# bicyclelab-manager-v4_0.net
KiCad netlist of a schematic drawn in EAGLE
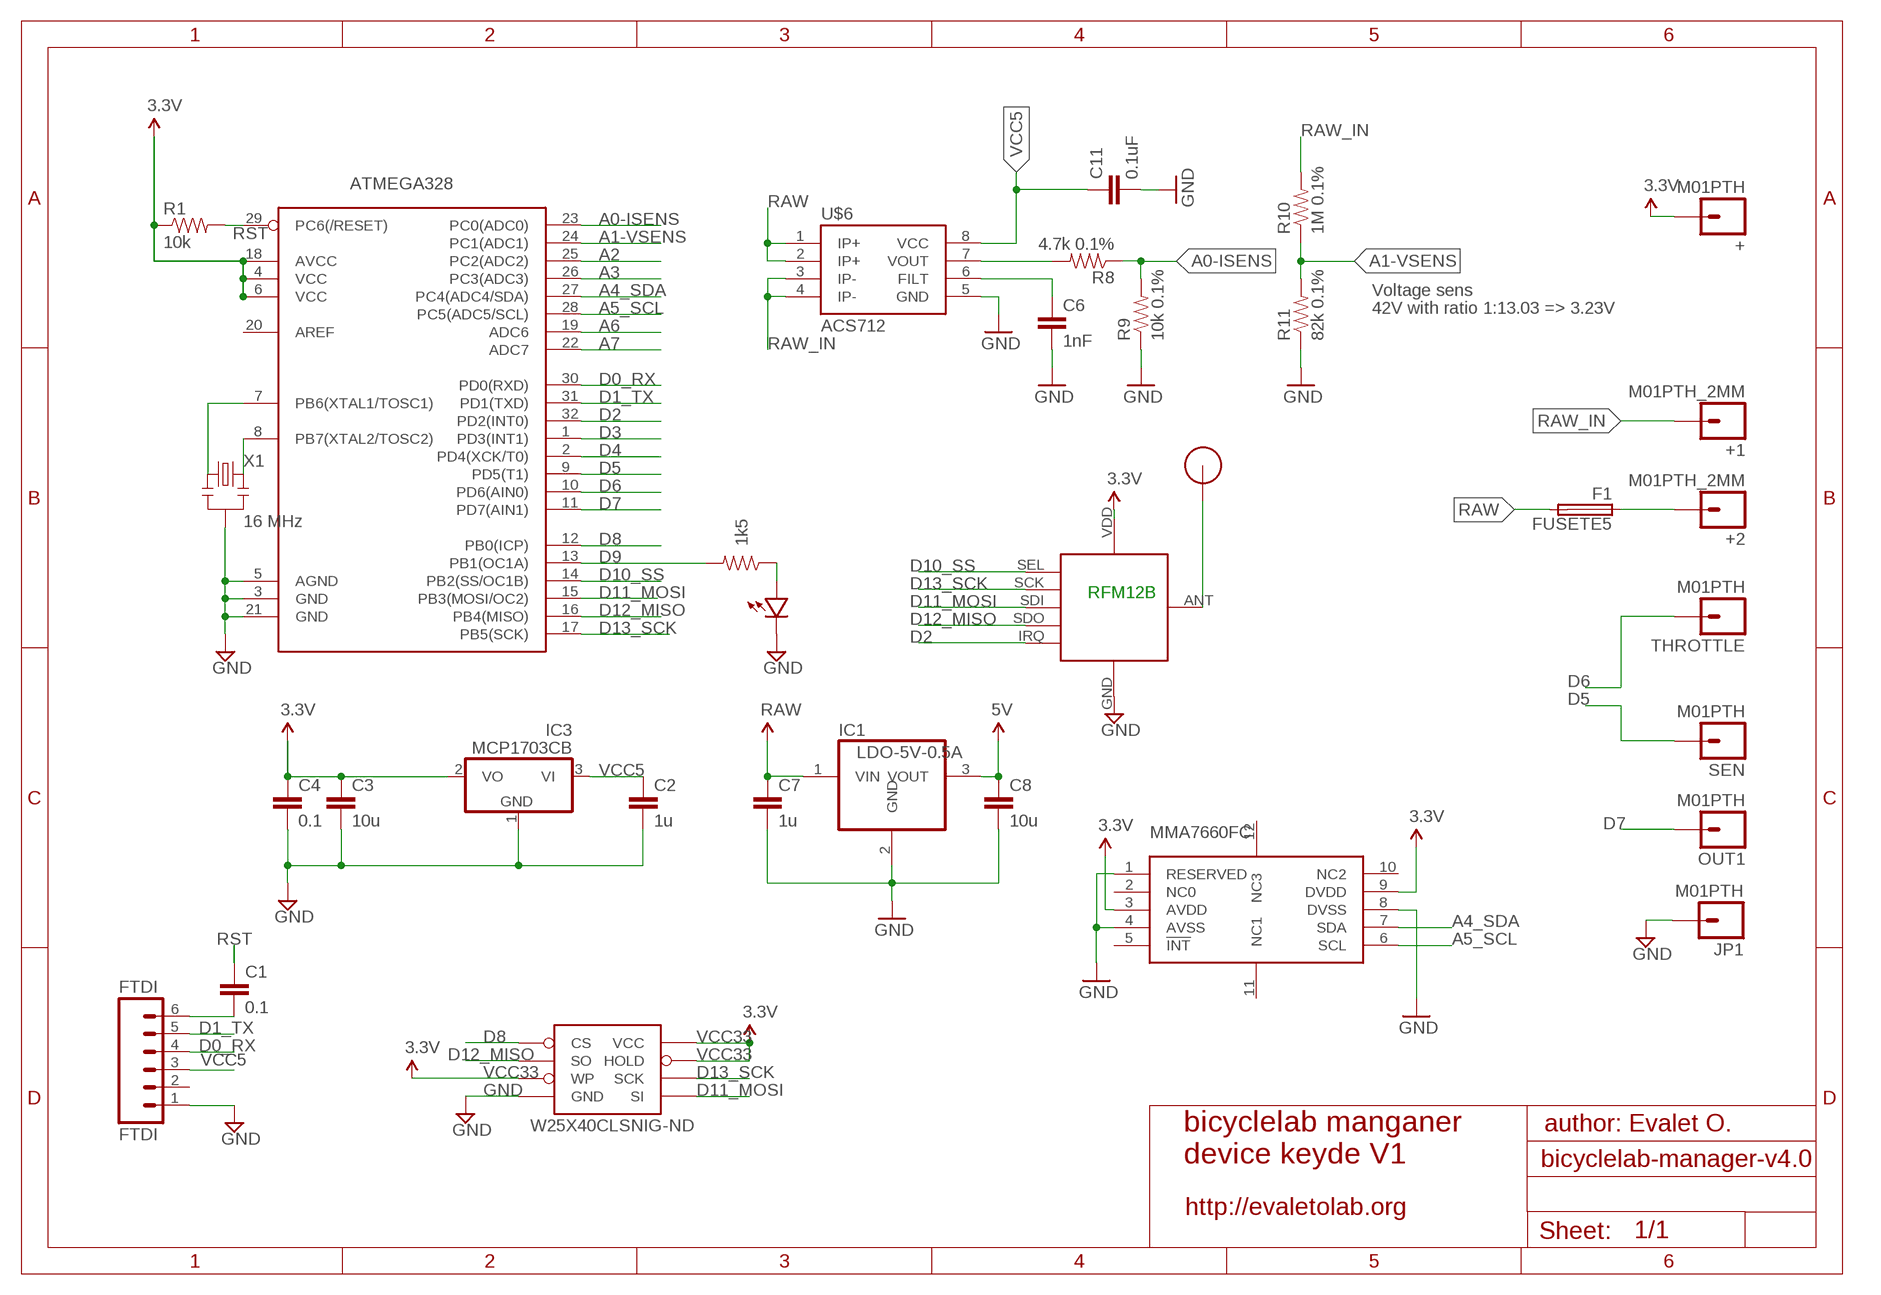
[diagram p0: schematic, sheet 1]

(export (version "E")
  (design (tool "Eeschema 10.0.6"))
  (components
    (comp (ref "+")
      (value "M01PTH")
      (footprint "eagle-import:1X01")
      (libsource (lib "eagle-import") (part "M01PTH"))
    )
    (comp (ref "+1")
      (value "M01PTH_2MM")
      (footprint "eagle-import:1X01_2MM")
      (libsource (lib "eagle-import") (part "M01PTH_2MM"))
    )
    (comp (ref "+2")
      (value "M01PTH_2MM")
      (footprint "eagle-import:1X01_2MM")
      (libsource (lib "eagle-import") (part "M01PTH_2MM"))
    )
    (comp (ref "ATMEGA328")
      (value "ATMega-328")
      (footprint "eagle-import:TQFP32-08")
      (libsource (lib "eagle-import") (part "ATMEGA168/328TQFP32"))
    )
    (comp (ref "C1")
      (value "0.1")
      (footprint "eagle-import:0603-CAP")
      (libsource (lib "eagle-import") (part "CAP0603-CAP"))
    )
    (comp (ref "C2")
      (value "1u")
      (footprint "eagle-import:0603-CAP")
      (libsource (lib "eagle-import") (part "CAP0603-CAP"))
    )
    (comp (ref "C3")
      (value "10u")
      (footprint "eagle-import:0805-CAP")
      (libsource (lib "eagle-import") (part "CAP0805-CAP"))
    )
    (comp (ref "C4")
      (value "0.1")
      (footprint "eagle-import:0603-CAP")
      (libsource (lib "eagle-import") (part "CAP0603-CAP"))
    )
    (comp (ref "C6")
      (value "1nF")
      (footprint "eagle-import:0805")
      (libsource (lib "eagle-import") (part "SparkFun_CAP0805"))
    )
    (comp (ref "C7")
      (value "1u")
      (footprint "eagle-import:0603-CAP")
      (libsource (lib "eagle-import") (part "CAP0603-CAP"))
    )
    (comp (ref "C8")
      (value "10u")
      (footprint "eagle-import:0805-CAP")
      (libsource (lib "eagle-import") (part "CAP0805-CAP"))
    )
    (comp (ref "C11")
      (value "0.1uF")
      (footprint "eagle-import:0805")
      (libsource (lib "eagle-import") (part "SparkFun_CAP0805"))
    )
    (comp (ref "F1")
      (value "FUSETE5")
      (footprint "eagle-import:TE5")
      (libsource (lib "eagle-import") (part "FUSETE5"))
    )
    (comp (ref "FTDI")
      (value "FTDI")
      (footprint "eagle-import:1X06")
      (libsource (lib "eagle-import") (part "M06SIP"))
    )
    (comp (ref "IC1")
      (value "LDO-5V-0.5A")
      (footprint "eagle-import:SOT223")
      (libsource (lib "eagle-import") (part "LDO-5V-0.5A"))
    )
    (comp (ref "IC3")
      (value "MCP1703CB")
      (footprint "eagle-import:SOT23")
      (libsource (lib "eagle-import") (part "MCP1703CB"))
    )
    (comp (ref "JP1")
      (value "M01PTH")
      (footprint "eagle-import:1X01")
      (libsource (lib "eagle-import") (part "M01PTH"))
    )
    (comp (ref "MMA7660FC")
      (value "MMA7660FC-DFN10")
      (footprint "eagle-import:DFN10")
      (libsource (lib "eagle-import") (part "MMA7660FC-DFN10"))
    )
    (comp (ref "OUT1")
      (value "M01PTH")
      (footprint "eagle-import:1X01")
      (libsource (lib "eagle-import") (part "M01PTH"))
    )
    (comp (ref "R1")
      (value "10k")
      (footprint "eagle-import:0603-RES")
      (libsource (lib "eagle-import") (part "RESISTOR0603-RES"))
    )
    (comp (ref "R2")
      (value "1k5")
      (footprint "eagle-import:0603-RES")
      (libsource (lib "eagle-import") (part "RESISTOR0603-RES"))
    )
    (comp (ref "R8")
      (value "4.7k 0.1%")
      (footprint "eagle-import:0805")
      (libsource (lib "eagle-import") (part "RESISTOR"))
    )
    (comp (ref "R9")
      (value "10k 0.1%")
      (footprint "eagle-import:0805")
      (libsource (lib "eagle-import") (part "RESISTOR"))
    )
    (comp (ref "R10")
      (value "1M 0.1%")
      (footprint "eagle-import:0805")
      (libsource (lib "eagle-import") (part "RESISTOR"))
    )
    (comp (ref "R11")
      (value "82k 0.1%")
      (footprint "eagle-import:0805")
      (libsource (lib "eagle-import") (part "RESISTOR"))
    )
    (comp (ref "RFM12B")
      (value "RFM12B_MINPADS")
      (footprint "eagle-import:RFM12B-MINPADS")
      (libsource (lib "eagle-import") (part "RFM12B_MINPADS"))
    )
    (comp (ref "SEN")
      (value "M01PTH")
      (footprint "eagle-import:1X01")
      (libsource (lib "eagle-import") (part "M01PTH"))
    )
    (comp (ref "THROTTLE")
      (value "M01PTH")
      (footprint "eagle-import:1X01")
      (libsource (lib "eagle-import") (part "M01PTH"))
    )
    (comp (ref "U$1")
      (value "RFM12B_ANTENNA")
      (footprint "eagle-import:RFM12B-ANTENNA")
      (libsource (lib "eagle-import") (part "RFM12B_ANTENNA"))
    )
    (comp (ref "U$2")
      (value "LED0603")
      (footprint "eagle-import:0603-LED")
      (libsource (lib "eagle-import") (part "LED0603"))
    )
    (comp (ref "U$6")
      (value "ACS712")
      (footprint "eagle-import:SO08")
      (libsource (lib "eagle-import") (part "ACS712"))
    )
    (comp (ref "W25X40CLSNIG-ND")
      (value "AT25F512BWIDE_5.3MM")
      (footprint "eagle-import:SO08WIDE")
      (libsource (lib "eagle-import") (part "AT25F512BWIDE_5.3MM"))
    )
    (comp (ref "X1")
      (value "16 MHz")
      (footprint "eagle-import:RESONATOR-SMD")
      (libsource (lib "eagle-import") (part "RESONATORSMD"))
    )
  )
  (nets
    (net (code "1") (name "/A2") (class "Default")
      (node (ref "ATMEGA328") (pin "25") (pinfunction "PC2(ADC2)_25") (pintype "bidirectional"))
    )
    (net (code "2") (name "/A3") (class "Default")
      (node (ref "ATMEGA328") (pin "26") (pinfunction "PC3(ADC3)_26") (pintype "bidirectional"))
    )
    (net (code "3") (name "/A4_SDA") (class "Default")
      (node (ref "ATMEGA328") (pin "27") (pinfunction "PC4(ADC4/SDA)_27") (pintype "bidirectional"))
      (node (ref "MMA7660FC") (pin "7") (pinfunction "SDA_7") (pintype "bidirectional"))
    )
    (net (code "4") (name "/A5_SCL") (class "Default")
      (node (ref "ATMEGA328") (pin "28") (pinfunction "PC5(ADC5/SCL)_28") (pintype "bidirectional"))
      (node (ref "MMA7660FC") (pin "6") (pinfunction "SCL_6") (pintype "bidirectional"))
    )
    (net (code "5") (name "/A6") (class "Default")
      (node (ref "ATMEGA328") (pin "19") (pinfunction "ADC6_19") (pintype "bidirectional"))
    )
    (net (code "6") (name "/A7") (class "Default")
      (node (ref "ATMEGA328") (pin "22") (pinfunction "ADC7_22") (pintype "bidirectional"))
    )
    (net (code "7") (name "/D0_RX") (class "Default")
      (node (ref "ATMEGA328") (pin "30") (pinfunction "PD0(RXD)_30") (pintype "bidirectional"))
      (node (ref "FTDI") (pin "4") (pinfunction "4_4") (pintype "passive"))
    )
    (net (code "8") (name "/D1_TX") (class "Default")
      (node (ref "ATMEGA328") (pin "31") (pinfunction "PD1(TXD)_31") (pintype "bidirectional"))
      (node (ref "FTDI") (pin "5") (pinfunction "5_5") (pintype "passive"))
    )
    (net (code "9") (name "/D2") (class "Default")
      (node (ref "ATMEGA328") (pin "32") (pinfunction "PD2(INT0)_32") (pintype "bidirectional"))
      (node (ref "RFM12B") (pin "IRQ") (pinfunction "IRQ_IRQ") (pintype "bidirectional"))
    )
    (net (code "10") (name "/D3") (class "Default")
      (node (ref "ATMEGA328") (pin "1") (pinfunction "PD3(INT1)_1") (pintype "bidirectional"))
    )
    (net (code "11") (name "/D4") (class "Default")
      (node (ref "ATMEGA328") (pin "2") (pinfunction "PD4(XCK/T0)_2") (pintype "bidirectional"))
    )
    (net (code "12") (name "/D5") (class "Default")
      (node (ref "ATMEGA328") (pin "9") (pinfunction "PD5(T1)_9") (pintype "bidirectional"))
      (node (ref "SEN") (pin "1") (pinfunction "1_1") (pintype "passive"))
    )
    (net (code "13") (name "/D6") (class "Default")
      (node (ref "ATMEGA328") (pin "10") (pinfunction "PD6(AIN0)_10") (pintype "bidirectional"))
      (node (ref "THROTTLE") (pin "1") (pinfunction "1_1") (pintype "passive"))
    )
    (net (code "14") (name "/D7") (class "Default")
      (node (ref "ATMEGA328") (pin "11") (pinfunction "PD7(AIN1)_11") (pintype "bidirectional"))
      (node (ref "OUT1") (pin "1") (pinfunction "1_1") (pintype "passive"))
    )
    (net (code "15") (name "/D8") (class "Default")
      (node (ref "ATMEGA328") (pin "12") (pinfunction "PB0(ICP)_12") (pintype "bidirectional"))
      (node (ref "W25X40CLSNIG-ND") (pin "1") (pinfunction "CS_1") (pintype "bidirectional"))
    )
    (net (code "16") (name "/D9") (class "Default")
      (node (ref "ATMEGA328") (pin "13") (pinfunction "PB1(OC1A)_13") (pintype "bidirectional"))
      (node (ref "R2") (pin "2") (pinfunction "2_2") (pintype "passive"))
    )
    (net (code "17") (name "/D10_SS") (class "Default")
      (node (ref "ATMEGA328") (pin "14") (pinfunction "PB2(SS/OC1B)_14") (pintype "bidirectional"))
      (node (ref "RFM12B") (pin "SEL") (pinfunction "SEL_SEL") (pintype "bidirectional"))
    )
    (net (code "18") (name "/D11_MOSI") (class "Default")
      (node (ref "ATMEGA328") (pin "15") (pinfunction "PB3(MOSI/OC2)_15") (pintype "bidirectional"))
      (node (ref "RFM12B") (pin "SDI") (pinfunction "SDI/MOSI_SDI") (pintype "bidirectional"))
      (node (ref "W25X40CLSNIG-ND") (pin "5") (pinfunction "SI_5") (pintype "bidirectional"))
    )
    (net (code "19") (name "/D12_MISO") (class "Default")
      (node (ref "ATMEGA328") (pin "16") (pinfunction "PB4(MISO)_16") (pintype "bidirectional"))
      (node (ref "RFM12B") (pin "SDO") (pinfunction "SDO/MISO_SDO") (pintype "bidirectional"))
      (node (ref "W25X40CLSNIG-ND") (pin "2") (pinfunction "SO_2") (pintype "bidirectional"))
    )
    (net (code "20") (name "/D13_SCK") (class "Default")
      (node (ref "ATMEGA328") (pin "17") (pinfunction "PB5(SCK)_17") (pintype "bidirectional"))
      (node (ref "RFM12B") (pin "SCK") (pinfunction "SCK_SCK") (pintype "bidirectional"))
      (node (ref "W25X40CLSNIG-ND") (pin "6") (pinfunction "SCK_6") (pintype "bidirectional"))
    )
    (net (code "21") (name "/RST") (class "Default")
      (node (ref "ATMEGA328") (pin "29") (pinfunction "PC6(/RESET)_29") (pintype "bidirectional"))
      (node (ref "C1") (pin "1") (pinfunction "1_1") (pintype "passive"))
      (node (ref "R1") (pin "2") (pinfunction "2_2") (pintype "passive"))
    )
    (net (code "22") (name "3.3V") (class "Default")
      (node (ref "+") (pin "1") (pinfunction "1_1") (pintype "passive"))
      (node (ref "ATMEGA328") (pin "18") (pinfunction "AVCC_18") (pintype "bidirectional"))
      (node (ref "ATMEGA328") (pin "4") (pinfunction "VCC_4") (pintype "bidirectional"))
      (node (ref "ATMEGA328") (pin "6") (pinfunction "VCC_6") (pintype "bidirectional"))
      (node (ref "C3") (pin "1") (pinfunction "1_1") (pintype "passive"))
      (node (ref "C4") (pin "1") (pinfunction "1_1") (pintype "passive"))
      (node (ref "IC3") (pin "2") (pinfunction "VO_2") (pintype "passive"))
      (node (ref "MMA7660FC") (pin "3") (pinfunction "AVDD_3") (pintype "bidirectional"))
      (node (ref "MMA7660FC") (pin "9") (pinfunction "DVDD_9") (pintype "bidirectional"))
      (node (ref "R1") (pin "1") (pinfunction "1_1") (pintype "passive"))
      (node (ref "RFM12B") (pin "VDD") (pinfunction "VDD_VDD") (pintype "bidirectional"))
      (node (ref "W25X40CLSNIG-ND") (pin "3") (pinfunction "WP_3") (pintype "bidirectional"))
      (node (ref "W25X40CLSNIG-ND") (pin "7") (pinfunction "HOLD_7") (pintype "bidirectional"))
      (node (ref "W25X40CLSNIG-ND") (pin "8") (pinfunction "VCC_8") (pintype "bidirectional"))
    )
    (net (code "23") (name "A0-ISENS") (class "Default")
      (node (ref "ATMEGA328") (pin "23") (pinfunction "PC0(ADC0)_23") (pintype "bidirectional"))
      (node (ref "R8") (pin "1") (pinfunction "1_1") (pintype "passive"))
      (node (ref "R9") (pin "2") (pinfunction "2_2") (pintype "passive"))
    )
    (net (code "24") (name "A1-VSENS") (class "Default")
      (node (ref "ATMEGA328") (pin "24") (pinfunction "PC1(ADC1)_24") (pintype "bidirectional"))
      (node (ref "R10") (pin "1") (pinfunction "1_1") (pintype "passive"))
      (node (ref "R11") (pin "2") (pinfunction "2_2") (pintype "passive"))
    )
    (net (code "25") (name "GND") (class "Default")
      (node (ref "ATMEGA328") (pin "21") (pinfunction "GND_21") (pintype "bidirectional"))
      (node (ref "ATMEGA328") (pin "3") (pinfunction "GND_3") (pintype "bidirectional"))
      (node (ref "ATMEGA328") (pin "5") (pinfunction "AGND_5") (pintype "bidirectional"))
      (node (ref "C11") (pin "2") (pinfunction "2_2") (pintype "passive"))
      (node (ref "C2") (pin "2") (pinfunction "2_2") (pintype "passive"))
      (node (ref "C3") (pin "2") (pinfunction "2_2") (pintype "passive"))
      (node (ref "C4") (pin "2") (pinfunction "2_2") (pintype "passive"))
      (node (ref "C6") (pin "2") (pinfunction "2_2") (pintype "passive"))
      (node (ref "C7") (pin "2") (pinfunction "2_2") (pintype "passive"))
      (node (ref "C8") (pin "2") (pinfunction "2_2") (pintype "passive"))
      (node (ref "FTDI") (pin "1") (pinfunction "1_1") (pintype "passive"))
      (node (ref "IC1") (pin "2") (pinfunction "GND_2") (pintype "power_in"))
      (node (ref "IC3") (pin "1") (pinfunction "GND_1") (pintype "passive"))
      (node (ref "JP1") (pin "1") (pinfunction "1_1") (pintype "passive"))
      (node (ref "MMA7660FC") (pin "1") (pinfunction "RESERVED_1") (pintype "bidirectional"))
      (node (ref "MMA7660FC") (pin "4") (pinfunction "AVSS_4") (pintype "bidirectional"))
      (node (ref "MMA7660FC") (pin "8") (pinfunction "DVSS_8") (pintype "bidirectional"))
      (node (ref "R11") (pin "1") (pinfunction "1_1") (pintype "passive"))
      (node (ref "R9") (pin "1") (pinfunction "1_1") (pintype "passive"))
      (node (ref "RFM12B") (pin "GND") (pinfunction "GND_GND") (pintype "bidirectional"))
      (node (ref "U$2") (pin "MINUS") (pinfunction "MINUS_MINUS") (pintype "passive"))
      (node (ref "U$6") (pin "5") (pinfunction "GND_5") (pintype "bidirectional"))
      (node (ref "W25X40CLSNIG-ND") (pin "4") (pinfunction "GND_4") (pintype "bidirectional"))
      (node (ref "X1") (pin "2") (pinfunction "2_2") (pintype "passive"))
    )
    (net (code "26") (name "Net-(+2-Pad1)") (class "Default")
      (node (ref "+2") (pin "1") (pinfunction "1_1") (pintype "passive"))
      (node (ref "F1") (pin "1") (pinfunction "1_1") (pintype "passive"))
    )
    (net (code "27") (name "Net-(ATMEGA328-PB6(XTAL1{slash}TOSC1))") (class "Default")
      (node (ref "ATMEGA328") (pin "7") (pinfunction "PB6(XTAL1/TOSC1)_7") (pintype "bidirectional"))
      (node (ref "X1") (pin "1") (pinfunction "1_1") (pintype "passive"))
    )
    (net (code "28") (name "Net-(ATMEGA328-PB7(XTAL2{slash}TOSC2))") (class "Default")
      (node (ref "ATMEGA328") (pin "8") (pinfunction "PB7(XTAL2/TOSC2)_8") (pintype "bidirectional"))
      (node (ref "X1") (pin "3") (pinfunction "3_3") (pintype "passive"))
    )
    (net (code "29") (name "Net-(C1-Pad2)") (class "Default")
      (node (ref "C1") (pin "2") (pinfunction "2_2") (pintype "passive"))
      (node (ref "FTDI") (pin "6") (pinfunction "6_6") (pintype "passive"))
    )
    (net (code "30") (name "Net-(R2-Pad1)") (class "Default")
      (node (ref "R2") (pin "1") (pinfunction "1_1") (pintype "passive"))
      (node (ref "U$2") (pin "PLUS") (pinfunction "PLUS_PLUS") (pintype "passive"))
    )
    (net (code "31") (name "Net-(U$1-1)") (class "Default")
      (node (ref "RFM12B") (pin "ANT") (pinfunction "ANT_ANT") (pintype "bidirectional"))
      (node (ref "U$1") (pin "P$1") (pinfunction "1_P$1") (pintype "bidirectional"))
    )
    (net (code "32") (name "Net-(U$6-FILT)") (class "Default")
      (node (ref "C6") (pin "1") (pinfunction "1_1") (pintype "passive"))
      (node (ref "U$6") (pin "6") (pinfunction "FILT_6") (pintype "bidirectional"))
    )
    (net (code "33") (name "Net-(U$6-VOUT)") (class "Default")
      (node (ref "R8") (pin "2") (pinfunction "2_2") (pintype "passive"))
      (node (ref "U$6") (pin "7") (pinfunction "VOUT_7") (pintype "bidirectional"))
    )
    (net (code "34") (name "RAW") (class "Default")
      (node (ref "C7") (pin "1") (pinfunction "1_1") (pintype "passive"))
      (node (ref "F1") (pin "2") (pinfunction "2_2") (pintype "passive"))
      (node (ref "IC1") (pin "1") (pinfunction "VIN_1") (pintype "input"))
      (node (ref "U$6") (pin "1") (pinfunction "IP+_1") (pintype "bidirectional"))
      (node (ref "U$6") (pin "2") (pinfunction "IP+_2") (pintype "bidirectional"))
    )
    (net (code "35") (name "RAW_IN") (class "Default")
      (node (ref "+1") (pin "1") (pinfunction "1_1") (pintype "passive"))
      (node (ref "R10") (pin "2") (pinfunction "2_2") (pintype "passive"))
      (node (ref "U$6") (pin "3") (pinfunction "IP-_3") (pintype "bidirectional"))
      (node (ref "U$6") (pin "4") (pinfunction "IP-_4") (pintype "bidirectional"))
    )
    (net (code "36") (name "VCC5") (class "Default")
      (node (ref "C11") (pin "1") (pinfunction "1_1") (pintype "passive"))
      (node (ref "C2") (pin "1") (pinfunction "1_1") (pintype "passive"))
      (node (ref "C8") (pin "1") (pinfunction "1_1") (pintype "passive"))
      (node (ref "FTDI") (pin "3") (pinfunction "3_3") (pintype "passive"))
      (node (ref "IC1") (pin "3") (pinfunction "VOUT_3") (pintype "output"))
      (node (ref "IC3") (pin "3") (pinfunction "VI_3") (pintype "input"))
      (node (ref "U$6") (pin "8") (pinfunction "VCC_8") (pintype "bidirectional"))
    )
    (net (code "37") (name "unconnected-(ATMEGA328-AREF-Pad20)") (class "Default")
      (node (ref "ATMEGA328") (pin "20") (pinfunction "AREF_20") (pintype "bidirectional"))
    )
    (net (code "38") (name "unconnected-(FTDI-Pad2)") (class "Default")
      (node (ref "FTDI") (pin "2") (pinfunction "2_2") (pintype "passive"))
    )
    (net (code "39") (name "unconnected-(MMA7660FC-NC0-Pad2)") (class "Default")
      (node (ref "MMA7660FC") (pin "2") (pinfunction "NC0_2") (pintype "bidirectional"))
    )
    (net (code "40") (name "unconnected-(MMA7660FC-NC1-Pad11)") (class "Default")
      (node (ref "MMA7660FC") (pin "11") (pinfunction "NC1_11") (pintype "bidirectional"))
    )
    (net (code "41") (name "unconnected-(MMA7660FC-NC2-Pad10)") (class "Default")
      (node (ref "MMA7660FC") (pin "10") (pinfunction "NC2_10") (pintype "bidirectional"))
    )
    (net (code "42") (name "unconnected-(MMA7660FC-NC3-Pad12)") (class "Default")
      (node (ref "MMA7660FC") (pin "12") (pinfunction "NC3_12") (pintype "bidirectional"))
    )
    (net (code "43") (name "unconnected-(MMA7660FC-~{INT}-Pad5)") (class "Default")
      (node (ref "MMA7660FC") (pin "5") (pinfunction "~{INT}_5") (pintype "bidirectional"))
    )
  )
)
